# Power.net
KiCad netlist of a schematic drawn in Altium Designer
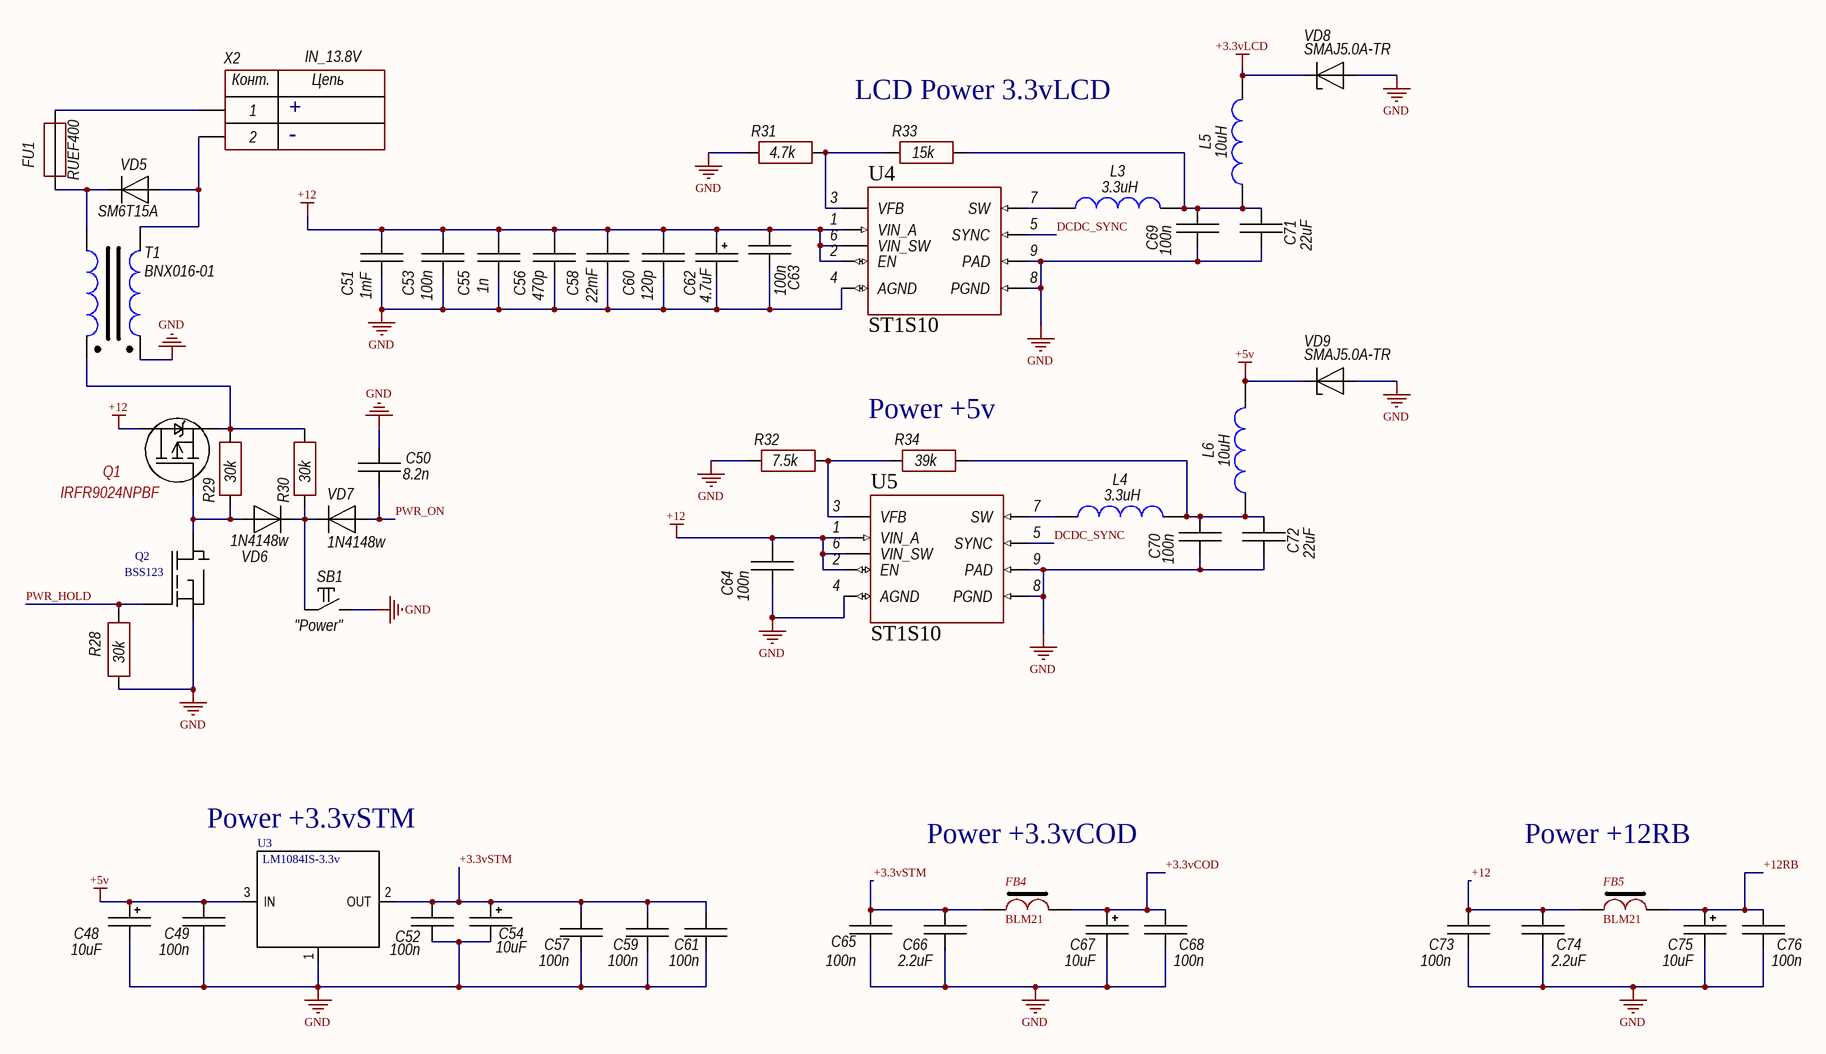
[diagram p0: Power.SchDoc]

(export (version "E")
  (design (tool "Eeschema 10.0.6"))
  (components
    (comp (ref "C48")
      (value "10uF")
      (footprint "standard:TANTAL_B")
      (libsource (lib "Discrete") (part "TantalCap"))
    )
    (comp (ref "C49")
      (value "100n")
      (footprint "standard:CH0805C")
      (libsource (lib "Discrete") (part "Capacitor"))
    )
    (comp (ref "C50")
      (value "8.2n")
      (footprint "standard:CH0805C")
      (libsource (lib "Discrete") (part "Capacitor"))
    )
    (comp (ref "C51")
      (value "1mF")
      (footprint "standard:CH0805C")
      (libsource (lib "Discrete") (part "Capacitor"))
    )
    (comp (ref "C52")
      (value "100n")
      (footprint "standard:CH0805C")
      (libsource (lib "Discrete") (part "Capacitor"))
    )
    (comp (ref "C53")
      (value "100n")
      (footprint "standard:CH0805C")
      (libsource (lib "Discrete") (part "Capacitor"))
    )
    (comp (ref "C54")
      (value "10uF")
      (footprint "standard:TANTAL_B")
      (libsource (lib "Discrete") (part "TantalCap"))
    )
    (comp (ref "C55")
      (value "1n")
      (footprint "standard:CH0805C")
      (libsource (lib "Discrete") (part "Capacitor"))
    )
    (comp (ref "C56")
      (value "470p")
      (footprint "standard:CH0805C")
      (libsource (lib "Discrete") (part "Capacitor"))
    )
    (comp (ref "C57")
      (value "100n")
      (footprint "standard:CH0805C")
      (libsource (lib "Discrete") (part "Capacitor"))
    )
    (comp (ref "C58")
      (value "22mF")
      (footprint "standard:CH1210C")
      (libsource (lib "Discrete") (part "Capacitor"))
    )
    (comp (ref "C59")
      (value "100n")
      (footprint "standard:CH0805C")
      (libsource (lib "Discrete") (part "Capacitor"))
    )
    (comp (ref "C60")
      (value "120p")
      (footprint "standard:CH0805C")
      (libsource (lib "Discrete") (part "Capacitor"))
    )
    (comp (ref "C61")
      (value "100n")
      (footprint "standard:CH0805C")
      (libsource (lib "Discrete") (part "Capacitor"))
    )
    (comp (ref "C62")
      (value "4.7uF")
      (footprint "standard:D6.3C2.5H11")
      (libsource (lib "Discrete") (part "AlumCap"))
    )
    (comp (ref "C63")
      (value "100n")
      (footprint "standard:CH0805C")
      (libsource (lib "Discrete") (part "Capacitor"))
    )
    (comp (ref "C64")
      (value "100n")
      (footprint "standard:CH0805C")
      (libsource (lib "Discrete") (part "Capacitor"))
    )
    (comp (ref "C65")
      (value "100n")
      (footprint "standard:CH0805C")
      (libsource (lib "Discrete") (part "Capacitor"))
    )
    (comp (ref "C66")
      (value "2.2uF")
      (footprint "standard:CH0805C")
      (libsource (lib "Discrete") (part "Capacitor"))
    )
    (comp (ref "C67")
      (value "10uF")
      (footprint "standard:TANTAL_B")
      (libsource (lib "Discrete") (part "TantalCap"))
    )
    (comp (ref "C68")
      (value "100n")
      (footprint "standard:CH0805C")
      (libsource (lib "Discrete") (part "Capacitor"))
    )
    (comp (ref "C69")
      (value "100n")
      (footprint "standard:CH0805C")
      (libsource (lib "Discrete") (part "Capacitor"))
    )
    (comp (ref "C70")
      (value "100n")
      (footprint "standard:CH0805C")
      (libsource (lib "Discrete") (part "Capacitor"))
    )
    (comp (ref "C71")
      (value "22uF")
      (footprint "standard:CH1210C")
      (libsource (lib "Discrete") (part "Capacitor"))
    )
    (comp (ref "C72")
      (value "22uF")
      (footprint "standard:CH1210C")
      (libsource (lib "Discrete") (part "Capacitor"))
    )
    (comp (ref "C73")
      (value "100n")
      (footprint "standard:CH0805C")
      (libsource (lib "Discrete") (part "Capacitor"))
    )
    (comp (ref "C74")
      (value "2.2uF")
      (footprint "standard:CH0805C")
      (libsource (lib "Discrete") (part "Capacitor"))
    )
    (comp (ref "C75")
      (value "10uF")
      (footprint "standard:TANTAL_B")
      (libsource (lib "Discrete") (part "TantalCap"))
    )
    (comp (ref "C76")
      (value "100n")
      (footprint "standard:CH0805C")
      (libsource (lib "Discrete") (part "Capacitor"))
    )
    (comp (ref "FB4") (value "BLM21") (footprint "CH0805L") (libsource (lib "Discrete") (part "FB-1")))
    (comp (ref "FB5") (value "BLM21") (footprint "CH0805L") (libsource (lib "Discrete") (part "FB-1")))
    (comp (ref "FU1")
      (value "RUEF400")
      (footprint "Fuse: Ruef400")
      (libsource (lib "Discrete") (part "Fuse"))
    )
    (comp (ref "L3")
      (value "3.3uH")
      (footprint "custom:IND: CDRH74")
      (libsource (lib "Discrete") (part "Inductor"))
    )
    (comp (ref "L4")
      (value "3.3uH")
      (footprint "custom:IND: CDRH74")
      (libsource (lib "Discrete") (part "Inductor"))
    )
    (comp (ref "L5")
      (value "10uH")
      (footprint "custom:IND: CDRH74")
      (libsource (lib "Discrete") (part "Inductor"))
    )
    (comp (ref "L6")
      (value "10uH")
      (footprint "custom:IND: CDRH74")
      (libsource (lib "Discrete") (part "Inductor"))
    )
    (comp (ref "Q1")
      (value "IRFR9024NPBF")
      (footprint "D2PAK_132")
      (libsource (lib "Transistor") (part "P-KANAL"))
    )
    (comp (ref "Q2") (value "BSS123") (footprint "SOT23_132") (libsource (lib "Transistor") (part "BSS123")))
    (comp (ref "R28") (value "30k") (footprint "standard:CH0805R") (libsource (lib "") (part "Resistor_1")))
    (comp (ref "R29") (value "30k") (footprint "standard:CH0805R") (libsource (lib "") (part "Resistor_1")))
    (comp (ref "R30") (value "30k") (footprint "standard:CH0805R") (libsource (lib "") (part "Resistor_1")))
    (comp (ref "R31")
      (value "4.7k")
      (footprint "standard:CH0805R")
      (libsource (lib "Discrete") (part "Resistor"))
    )
    (comp (ref "R32")
      (value "7.5k")
      (footprint "standard:CH0805R")
      (libsource (lib "Discrete") (part "Resistor"))
    )
    (comp (ref "R33")
      (value "15k")
      (footprint "standard:CH0805R")
      (libsource (lib "Discrete") (part "Resistor"))
    )
    (comp (ref "R34")
      (value "39k")
      (footprint "standard:CH0805R")
      (libsource (lib "Discrete") (part "Resistor"))
    )
    (comp (ref "SB1")
      (value "\"Power\"")
      (footprint "custom:BUT: 6x6")
      (description "6x6 mm")
      (libsource (lib "Connectors") (part "Tactile switches"))
    )
    (comp (ref "T1")
      (value "BNX016-01")
      (footprint "BNX016-01")
      (fields (field (name "MANUFACTURER") "Murata Electronics North America"))
      (libsource (lib "Transformers") (part "EMI bead"))
    )
    (comp (ref "U3")
      (value "LM1084IS-3.3v")
      (footprint "TO-263-3(123)")
      (libsource (lib "Power Supplies") (part "LM1084"))
    )
    (comp (ref "U4") (value "ST1S10") (footprint "8-SOIC (PAD)") (libsource (lib "Digital") (part "ST1S10")))
    (comp (ref "U5") (value "ST1S10") (footprint "8-SOIC (PAD)") (libsource (lib "Digital") (part "ST1S10")))
    (comp (ref "VD5") (value "SM6T15A") (footprint "standard:SMB") (libsource (lib "Diods") (part "Diod")))
    (comp (ref "VD6")
      (value "1N4148w")
      (footprint "standard:SOD123F")
      (libsource (lib "Diods") (part "Diod"))
    )
    (comp (ref "VD7")
      (value "1N4148w")
      (footprint "standard:SOD123F")
      (libsource (lib "Diods") (part "Diod"))
    )
    (comp (ref "VD8")
      (value "SMAJ5.0A-TR")
      (footprint "standard:SMA")
      (libsource (lib "") (part "Diod Zener_1"))
    )
    (comp (ref "VD9")
      (value "SMAJ5.0A-TR")
      (footprint "standard:SMA")
      (libsource (lib "Diods") (part "Diod Zener"))
    )
    (comp (ref "X2")
      (value "IN_13.8V")
      (footprint "custom:CON: WF-02")
      (libsource (lib "Connectors") (part "2-Connector"))
    )
  )
  (nets
    (net (code "1") (name "+3.3vLCD") (class "Default")
      (node (ref "L5") (pin "1") (pinfunction "1_1") (pintype "passive"))
      (node (ref "VD8") (pin "2") (pinfunction "C_2") (pintype "passive"))
    )
    (net (code "2") (name "+5v") (class "Default")
      (node (ref "C48") (pin "1") (pinfunction "1_1") (pintype "power_in"))
      (node (ref "C49") (pin "2") (pinfunction "2_2") (pintype "power_in"))
      (node (ref "L6") (pin "1") (pinfunction "1_1") (pintype "passive"))
      (node (ref "U3") (pin "3") (pinfunction "IN_3") (pintype "passive"))
      (node (ref "VD9") (pin "2") (pinfunction "C_2") (pintype "passive"))
    )
    (net (code "3") (name "+12") (class "Default")
      (node (ref "C51") (pin "2") (pinfunction "2_2") (pintype "power_in"))
      (node (ref "C53") (pin "2") (pinfunction "2_2") (pintype "power_in"))
      (node (ref "C55") (pin "2") (pinfunction "2_2") (pintype "power_in"))
      (node (ref "C56") (pin "2") (pinfunction "2_2") (pintype "power_in"))
      (node (ref "C58") (pin "2") (pinfunction "2_2") (pintype "power_in"))
      (node (ref "C60") (pin "2") (pinfunction "2_2") (pintype "power_in"))
      (node (ref "C62") (pin "1") (pinfunction "1_1") (pintype "power_in"))
      (node (ref "C63") (pin "2") (pinfunction "2_2") (pintype "power_in"))
      (node (ref "C64") (pin "2") (pinfunction "2_2") (pintype "power_in"))
      (node (ref "C73") (pin "2") (pinfunction "2_2") (pintype "power_in"))
      (node (ref "C74") (pin "2") (pinfunction "2_2") (pintype "power_in"))
      (node (ref "FB5") (pin "2") (pinfunction "2_2") (pintype "passive"))
      (node (ref "Q1") (pin "3") (pinfunction "Сток(Drain)_3") (pintype "passive"))
      (node (ref "U4") (pin "1") (pinfunction "VIN_A_1") (pintype "input"))
      (node (ref "U4") (pin "2") (pinfunction "EN_2") (pintype "bidirectional"))
      (node (ref "U4") (pin "6") (pinfunction "VIN_SW_6") (pintype "power_in"))
      (node (ref "U5") (pin "1") (pinfunction "VIN_A_1") (pintype "input"))
      (node (ref "U5") (pin "2") (pinfunction "EN_2") (pintype "bidirectional"))
      (node (ref "U5") (pin "6") (pinfunction "VIN_SW_6") (pintype "power_in"))
    )
    (net (code "4") (name "/+3.3vCOD") (class "Default")
      (node (ref "C67") (pin "1") (pinfunction "1_1") (pintype "power_in"))
      (node (ref "C68") (pin "2") (pinfunction "2_2") (pintype "power_in"))
      (node (ref "FB4") (pin "1") (pinfunction "1_1") (pintype "passive"))
    )
    (net (code "5") (name "/+3.3vSTM") (class "Default")
      (node (ref "C52") (pin "2") (pinfunction "2_2") (pintype "power_in"))
      (node (ref "C54") (pin "1") (pinfunction "1_1") (pintype "power_in"))
      (node (ref "C57") (pin "2") (pinfunction "2_2") (pintype "power_in"))
      (node (ref "C59") (pin "2") (pinfunction "2_2") (pintype "power_in"))
      (node (ref "C61") (pin "2") (pinfunction "2_2") (pintype "power_in"))
      (node (ref "C65") (pin "2") (pinfunction "2_2") (pintype "power_in"))
      (node (ref "C66") (pin "2") (pinfunction "2_2") (pintype "power_in"))
      (node (ref "FB4") (pin "2") (pinfunction "2_2") (pintype "passive"))
      (node (ref "U3") (pin "2") (pinfunction "OUT_2") (pintype "passive"))
    )
    (net (code "6") (name "/+12RB") (class "Default")
      (node (ref "C75") (pin "1") (pinfunction "1_1") (pintype "power_in"))
      (node (ref "C76") (pin "2") (pinfunction "2_2") (pintype "power_in"))
      (node (ref "FB5") (pin "1") (pinfunction "1_1") (pintype "passive"))
    )
    (net (code "7") (name "/DCDC_SYNC") (class "Default")
      (node (ref "U4") (pin "5") (pinfunction "SYNC_5") (pintype "input"))
      (node (ref "U5") (pin "5") (pinfunction "SYNC_5") (pintype "input"))
    )
    (net (code "8") (name "/PWR_HOLD") (class "Default")
      (node (ref "Q2") (pin "1") (pinfunction "G_1") (pintype "passive"))
      (node (ref "R28") (pin "2") (pinfunction "2_2") (pintype "passive"))
    )
    (net (code "9") (name "/PWR_ON") (class "Default")
      (node (ref "C50") (pin "1") (pinfunction "1_1") (pintype "power_in"))
      (node (ref "VD7") (pin "1") (pinfunction "1_1") (pintype "passive"))
    )
    (net (code "10") (name "GND") (class "Default")
      (node (ref "C48") (pin "2") (pinfunction "2_2") (pintype "power_in"))
      (node (ref "C49") (pin "1") (pinfunction "1_1") (pintype "power_in"))
      (node (ref "C50") (pin "2") (pinfunction "2_2") (pintype "power_in"))
      (node (ref "C51") (pin "1") (pinfunction "1_1") (pintype "power_in"))
      (node (ref "C52") (pin "1") (pinfunction "1_1") (pintype "power_in"))
      (node (ref "C53") (pin "1") (pinfunction "1_1") (pintype "power_in"))
      (node (ref "C54") (pin "2") (pinfunction "2_2") (pintype "power_in"))
      (node (ref "C55") (pin "1") (pinfunction "1_1") (pintype "power_in"))
      (node (ref "C56") (pin "1") (pinfunction "1_1") (pintype "power_in"))
      (node (ref "C57") (pin "1") (pinfunction "1_1") (pintype "power_in"))
      (node (ref "C58") (pin "1") (pinfunction "1_1") (pintype "power_in"))
      (node (ref "C59") (pin "1") (pinfunction "1_1") (pintype "power_in"))
      (node (ref "C60") (pin "1") (pinfunction "1_1") (pintype "power_in"))
      (node (ref "C61") (pin "1") (pinfunction "1_1") (pintype "power_in"))
      (node (ref "C62") (pin "2") (pinfunction "2_2") (pintype "power_in"))
      (node (ref "C63") (pin "1") (pinfunction "1_1") (pintype "power_in"))
      (node (ref "C64") (pin "1") (pinfunction "1_1") (pintype "power_in"))
      (node (ref "C65") (pin "1") (pinfunction "1_1") (pintype "power_in"))
      (node (ref "C66") (pin "1") (pinfunction "1_1") (pintype "power_in"))
      (node (ref "C67") (pin "2") (pinfunction "2_2") (pintype "power_in"))
      (node (ref "C68") (pin "1") (pinfunction "1_1") (pintype "power_in"))
      (node (ref "C69") (pin "1") (pinfunction "1_1") (pintype "power_in"))
      (node (ref "C70") (pin "1") (pinfunction "1_1") (pintype "power_in"))
      (node (ref "C71") (pin "1") (pinfunction "1_1") (pintype "power_in"))
      (node (ref "C72") (pin "1") (pinfunction "1_1") (pintype "power_in"))
      (node (ref "C73") (pin "1") (pinfunction "1_1") (pintype "power_in"))
      (node (ref "C74") (pin "1") (pinfunction "1_1") (pintype "power_in"))
      (node (ref "C75") (pin "2") (pinfunction "2_2") (pintype "power_in"))
      (node (ref "C76") (pin "1") (pinfunction "1_1") (pintype "power_in"))
      (node (ref "Q2") (pin "2") (pinfunction "S_2") (pintype "passive"))
      (node (ref "R28") (pin "1") (pinfunction "1_1") (pintype "passive"))
      (node (ref "R31") (pin "1") (pinfunction "1_1") (pintype "passive"))
      (node (ref "R32") (pin "1") (pinfunction "1_1") (pintype "passive"))
      (node (ref "SB1") (pin "2") (pinfunction "2_2") (pintype "passive"))
      (node (ref "T1") (pin "3") (pinfunction "3_3") (pintype "passive"))
      (node (ref "U3") (pin "1") (pintype "passive"))
      (node (ref "U4") (pin "4") (pinfunction "AGND_4") (pintype "bidirectional"))
      (node (ref "U4") (pin "8") (pinfunction "PGND_8") (pintype "input"))
      (node (ref "U4") (pin "9") (pinfunction "PAD_9") (pintype "input"))
      (node (ref "U5") (pin "4") (pinfunction "AGND_4") (pintype "bidirectional"))
      (node (ref "U5") (pin "8") (pinfunction "PGND_8") (pintype "input"))
      (node (ref "U5") (pin "9") (pinfunction "PAD_9") (pintype "input"))
      (node (ref "VD8") (pin "1") (pinfunction "A_1") (pintype "passive"))
      (node (ref "VD9") (pin "1") (pinfunction "A_1") (pintype "passive"))
    )
    (net (code "11") (name "Net-(C69-Pad2)") (class "Default")
      (node (ref "C69") (pin "2") (pinfunction "2_2") (pintype "power_in"))
      (node (ref "C71") (pin "2") (pinfunction "2_2") (pintype "power_in"))
      (node (ref "L3") (pin "1") (pinfunction "1_1") (pintype "passive"))
      (node (ref "L5") (pin "2") (pinfunction "2_2") (pintype "passive"))
      (node (ref "R33") (pin "2") (pinfunction "2_2") (pintype "passive"))
    )
    (net (code "12") (name "Net-(C70-Pad2)") (class "Default")
      (node (ref "C70") (pin "2") (pinfunction "2_2") (pintype "power_in"))
      (node (ref "C72") (pin "2") (pinfunction "2_2") (pintype "power_in"))
      (node (ref "L4") (pin "1") (pinfunction "1_1") (pintype "passive"))
      (node (ref "L6") (pin "2") (pinfunction "2_2") (pintype "passive"))
      (node (ref "R34") (pin "2") (pinfunction "2_2") (pintype "passive"))
    )
    (net (code "13") (name "Net-(FU1-Pad1)") (class "Default")
      (node (ref "FU1") (pin "1") (pinfunction "1_1") (pintype "passive"))
      (node (ref "T1") (pin "2") (pinfunction "2_2") (pintype "passive"))
      (node (ref "VD5") (pin "2") (pinfunction "2_2") (pintype "passive"))
    )
    (net (code "14") (name "Net-(FU1-Pad2)") (class "Default")
      (node (ref "FU1") (pin "2") (pinfunction "2_2") (pintype "passive"))
      (node (ref "X2") (pin "1") (pinfunction "1_1") (pintype "passive"))
    )
    (net (code "15") (name "Net-(Q1-I)") (class "Default")
      (node (ref "Q1") (pin "2") (pinfunction "I_2") (pintype "passive"))
      (node (ref "R29") (pin "2") (pinfunction "2_2") (pintype "passive"))
      (node (ref "R30") (pin "2") (pinfunction "2_2") (pintype "passive"))
      (node (ref "T1") (pin "1") (pinfunction "1_1") (pintype "passive"))
    )
    (net (code "16") (name "Net-(Q1-Затвор(Gate))") (class "Default")
      (node (ref "Q1") (pin "1") (pinfunction "Затвор(Gate)_1") (pintype "passive"))
      (node (ref "Q2") (pin "3") (pinfunction "D_3") (pintype "passive"))
      (node (ref "R29") (pin "1") (pinfunction "1_1") (pintype "passive"))
      (node (ref "VD6") (pin "1") (pinfunction "1_1") (pintype "passive"))
    )
    (net (code "17") (name "Net-(R30-Pad1)") (class "Default")
      (node (ref "R30") (pin "1") (pinfunction "1_1") (pintype "passive"))
      (node (ref "SB1") (pin "1") (pinfunction "1_1") (pintype "passive"))
      (node (ref "VD6") (pin "2") (pinfunction "2_2") (pintype "passive"))
      (node (ref "VD7") (pin "2") (pinfunction "2_2") (pintype "passive"))
    )
    (net (code "18") (name "Net-(T1-Pad4)") (class "Default")
      (node (ref "T1") (pin "4") (pinfunction "4_4") (pintype "passive"))
      (node (ref "VD5") (pin "1") (pinfunction "1_1") (pintype "passive"))
      (node (ref "X2") (pin "2") (pinfunction "2_2") (pintype "passive"))
    )
    (net (code "19") (name "Net-(U4-SW)") (class "Default")
      (node (ref "L3") (pin "2") (pinfunction "2_2") (pintype "passive"))
      (node (ref "U4") (pin "7") (pinfunction "SW_7") (pintype "input"))
    )
    (net (code "20") (name "Net-(U4-VFB)") (class "Default")
      (node (ref "R31") (pin "2") (pinfunction "2_2") (pintype "passive"))
      (node (ref "R33") (pin "1") (pinfunction "1_1") (pintype "passive"))
      (node (ref "U4") (pin "3") (pinfunction "VFB_3") (pintype "power_in"))
    )
    (net (code "21") (name "Net-(U5-SW)") (class "Default")
      (node (ref "L4") (pin "2") (pinfunction "2_2") (pintype "passive"))
      (node (ref "U5") (pin "7") (pinfunction "SW_7") (pintype "input"))
    )
    (net (code "22") (name "Net-(U5-VFB)") (class "Default")
      (node (ref "R32") (pin "2") (pinfunction "2_2") (pintype "passive"))
      (node (ref "R34") (pin "1") (pinfunction "1_1") (pintype "passive"))
      (node (ref "U5") (pin "3") (pinfunction "VFB_3") (pintype "power_in"))
    )
  )
)
